# Jam.net
KiCad netlist of a schematic drawn in EAGLE
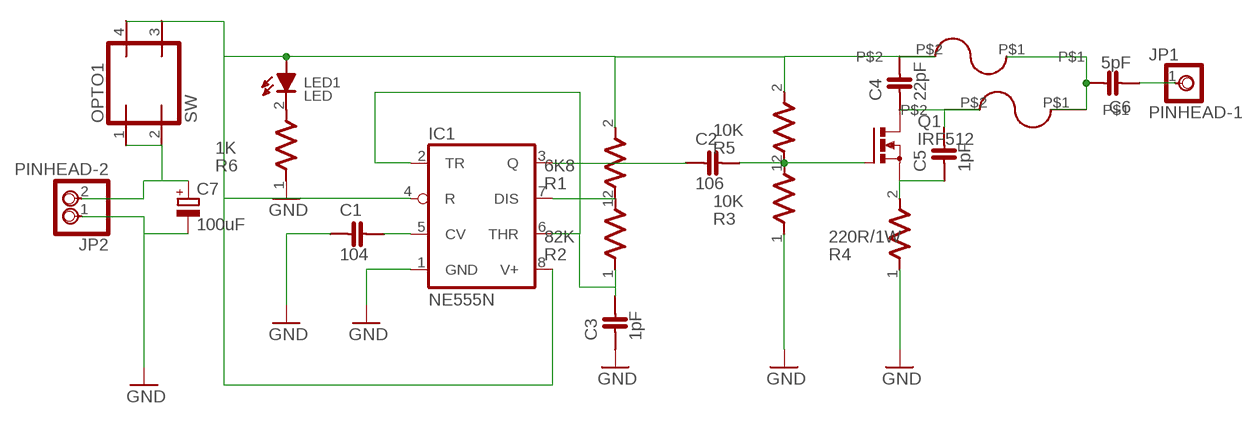
[diagram p0: schematic, sheet 1]

(export (version "E")
  (design (tool "Eeschema 10.0.6"))
  (components
    (comp (ref "2.2NH")
      (value "L5")
      (footprint "eagle-import:L5")
      (libsource (lib "eagle-import") (part "L5"))
    )
    (comp (ref "C1")
      (value "104")
      (footprint "eagle-import:CAP-NP5")
      (libsource (lib "eagle-import") (part "CAP-NP5"))
    )
    (comp (ref "C2")
      (value "106")
      (footprint "eagle-import:CAP-NP5")
      (libsource (lib "eagle-import") (part "CAP-NP5"))
    )
    (comp (ref "C3")
      (value "1pF")
      (footprint "eagle-import:CAP-NP5")
      (libsource (lib "eagle-import") (part "CAP-NP5"))
    )
    (comp (ref "C4")
      (value "22pF")
      (footprint "eagle-import:CAP-NP5")
      (libsource (lib "eagle-import") (part "CAP-NP5"))
    )
    (comp (ref "C5")
      (value "1pF")
      (footprint "eagle-import:CAP-NP5")
      (libsource (lib "eagle-import") (part "CAP-NP5"))
    )
    (comp (ref "C6")
      (value "5pF")
      (footprint "eagle-import:CAP-NP5")
      (libsource (lib "eagle-import") (part "CAP-NP5"))
    )
    (comp (ref "C7")
      (value "100uF")
      (footprint "eagle-import:E2,5-7")
      (libsource (lib "eagle-import") (part "CPOL-EUE2.5-7"))
    )
    (comp (ref "IC1")
      (value "NE555N")
      (footprint "eagle-import:DIL08")
      (libsource (lib "eagle-import") (part "555NNE"))
    )
    (comp (ref "JP1")
      (value "PINHEAD-1")
      (footprint "eagle-import:PINHEAD-1")
      (libsource (lib "eagle-import") (part "PINHEAD-1"))
    )
    (comp (ref "JP2")
      (value "PINHEAD-2")
      (footprint "eagle-import:PINHEAD-2")
      (libsource (lib "eagle-import") (part "PINHEAD-2"))
    )
    (comp (ref "LED1")
      (value "LED")
      (footprint "eagle-import:LED5")
      (libsource (lib "eagle-import") (part "LED-5"))
    )
    (comp (ref "OPTO1")
      (value "SW")
      (footprint "eagle-import:DIL-04")
      (libsource (lib "eagle-import") (part "PC817"))
    )
    (comp (ref "Q1")
      (value "IRF512")
      (footprint "eagle-import:TO220BV")
      (libsource (lib "eagle-import") (part "IRF512"))
    )
    (comp (ref "R1")
      (value "6K8")
      (footprint "eagle-import:R-7,5")
      (libsource (lib "eagle-import") (part "R-7,5"))
    )
    (comp (ref "R2")
      (value "82K")
      (footprint "eagle-import:R-7,5")
      (libsource (lib "eagle-import") (part "R-7,5"))
    )
    (comp (ref "R3")
      (value "10K")
      (footprint "eagle-import:R-7,5")
      (libsource (lib "eagle-import") (part "R-7,5"))
    )
    (comp (ref "R4")
      (value "220R/1W")
      (footprint "eagle-import:R-10")
      (libsource (lib "eagle-import") (part "R-10"))
    )
    (comp (ref "R5")
      (value "10K")
      (footprint "eagle-import:R-7,5")
      (libsource (lib "eagle-import") (part "R-7,5"))
    )
    (comp (ref "R6")
      (value "1K")
      (footprint "eagle-import:R-7,5")
      (libsource (lib "eagle-import") (part "R-7,5"))
    )
    (comp (ref "U$1") (value "L5") (footprint "eagle-import:L5") (libsource (lib "eagle-import") (part "L5")))
  )
  (nets
    (net (code "1") (name "GND") (class "Default")
      (node (ref "C1") (pin "1") (pinfunction "1_1") (pintype "passive"))
      (node (ref "C3") (pin "1") (pinfunction "1_1") (pintype "passive"))
      (node (ref "C7") (pin "-") (pinfunction "-_-") (pintype "passive"))
      (node (ref "IC1") (pin "1") (pinfunction "GND_1") (pintype "power_in"))
      (node (ref "JP2") (pin "1") (pinfunction "1_1") (pintype "passive"))
      (node (ref "R3") (pin "1") (pinfunction "1_1") (pintype "passive"))
      (node (ref "R4") (pin "1") (pinfunction "1_1") (pintype "passive"))
      (node (ref "R6") (pin "1") (pinfunction "1_1") (pintype "passive"))
    )
    (net (code "2") (name "Net-(2.2NH-PadP$1)") (class "Default")
      (node (ref "2.2NH") (pin "P$1") (pinfunction "P$1_P$1") (pintype "bidirectional"))
      (node (ref "C6") (pin "2") (pinfunction "2_2") (pintype "passive"))
      (node (ref "U$1") (pin "P$1") (pinfunction "P$1_P$1") (pintype "bidirectional"))
    )
    (net (code "3") (name "Net-(C2-Pad2)") (class "Default")
      (node (ref "C2") (pin "2") (pinfunction "2_2") (pintype "passive"))
      (node (ref "Q1") (pin "G") (pinfunction "G_G") (pintype "passive"))
      (node (ref "R3") (pin "2") (pinfunction "2_2") (pintype "passive"))
      (node (ref "R5") (pin "1") (pinfunction "1_1") (pintype "passive"))
    )
    (net (code "4") (name "Net-(C4-Pad1)") (class "Default")
      (node (ref "C4") (pin "1") (pinfunction "1_1") (pintype "passive"))
      (node (ref "C5") (pin "2") (pinfunction "2_2") (pintype "passive"))
      (node (ref "Q1") (pin "D") (pinfunction "D_D") (pintype "passive"))
      (node (ref "U$1") (pin "P$2") (pinfunction "P$2_P$2") (pintype "bidirectional"))
    )
    (net (code "5") (name "Net-(C6-Pad1)") (class "Default")
      (node (ref "C6") (pin "1") (pinfunction "1_1") (pintype "passive"))
      (node (ref "JP1") (pin "1") (pinfunction "1_1") (pintype "passive"))
    )
    (net (code "6") (name "Net-(IC1-CV)") (class "Default")
      (node (ref "C1") (pin "2") (pinfunction "2_2") (pintype "passive"))
      (node (ref "IC1") (pin "5") (pinfunction "CV_5") (pintype "input"))
    )
    (net (code "7") (name "Net-(IC1-DIS)") (class "Default")
      (node (ref "IC1") (pin "7") (pinfunction "DIS_7") (pintype "input"))
      (node (ref "R1") (pin "1") (pinfunction "1_1") (pintype "passive"))
      (node (ref "R2") (pin "2") (pinfunction "2_2") (pintype "passive"))
    )
    (net (code "8") (name "Net-(IC1-Q)") (class "Default")
      (node (ref "C2") (pin "1") (pinfunction "1_1") (pintype "passive"))
      (node (ref "IC1") (pin "3") (pinfunction "Q_3") (pintype "output"))
    )
    (net (code "9") (name "Net-(IC1-R)") (class "Default")
      (node (ref "2.2NH") (pin "P$2") (pinfunction "P$2_P$2") (pintype "bidirectional"))
      (node (ref "C4") (pin "2") (pinfunction "2_2") (pintype "passive"))
      (node (ref "IC1") (pin "4") (pinfunction "R_4") (pintype "input"))
      (node (ref "IC1") (pin "8") (pinfunction "V+_8") (pintype "power_in"))
      (node (ref "LED1") (pin "A") (pinfunction "A_A") (pintype "passive"))
      (node (ref "OPTO1") (pin "3") (pinfunction "EMI_3") (pintype "passive"))
      (node (ref "OPTO1") (pin "4") (pinfunction "COL_4") (pintype "passive"))
      (node (ref "R1") (pin "2") (pinfunction "2_2") (pintype "passive"))
      (node (ref "R5") (pin "2") (pinfunction "2_2") (pintype "passive"))
    )
    (net (code "10") (name "Net-(IC1-THR)") (class "Default")
      (node (ref "C3") (pin "2") (pinfunction "2_2") (pintype "passive"))
      (node (ref "IC1") (pin "2") (pinfunction "TR_2") (pintype "input"))
      (node (ref "IC1") (pin "6") (pinfunction "THR_6") (pintype "input"))
      (node (ref "R2") (pin "1") (pinfunction "1_1") (pintype "passive"))
    )
    (net (code "11") (name "Net-(LED1-PadK)") (class "Default")
      (node (ref "LED1") (pin "K") (pinfunction "K_K") (pintype "passive"))
      (node (ref "R6") (pin "2") (pinfunction "2_2") (pintype "passive"))
    )
    (net (code "12") (name "Net-(OPTO1-A)") (class "Default")
      (node (ref "C7") (pin "+") (pinfunction "+_+") (pintype "passive"))
      (node (ref "JP2") (pin "2") (pinfunction "2_2") (pintype "passive"))
      (node (ref "OPTO1") (pin "1") (pinfunction "A_1") (pintype "passive"))
      (node (ref "OPTO1") (pin "2") (pinfunction "C_2") (pintype "passive"))
    )
    (net (code "13") (name "Net-(R4-3)") (class "Default")
      (node (ref "C5") (pin "1") (pinfunction "1_1") (pintype "passive"))
      (node (ref "Q1") (pin "S") (pinfunction "S_S") (pintype "passive"))
      (node (ref "R4") (pin "2") (pinfunction "3_2") (pintype "passive"))
    )
  )
)
